# FMC_130MSPS_4CH.net
KiCad netlist of a schematic drawn in Altium Designer
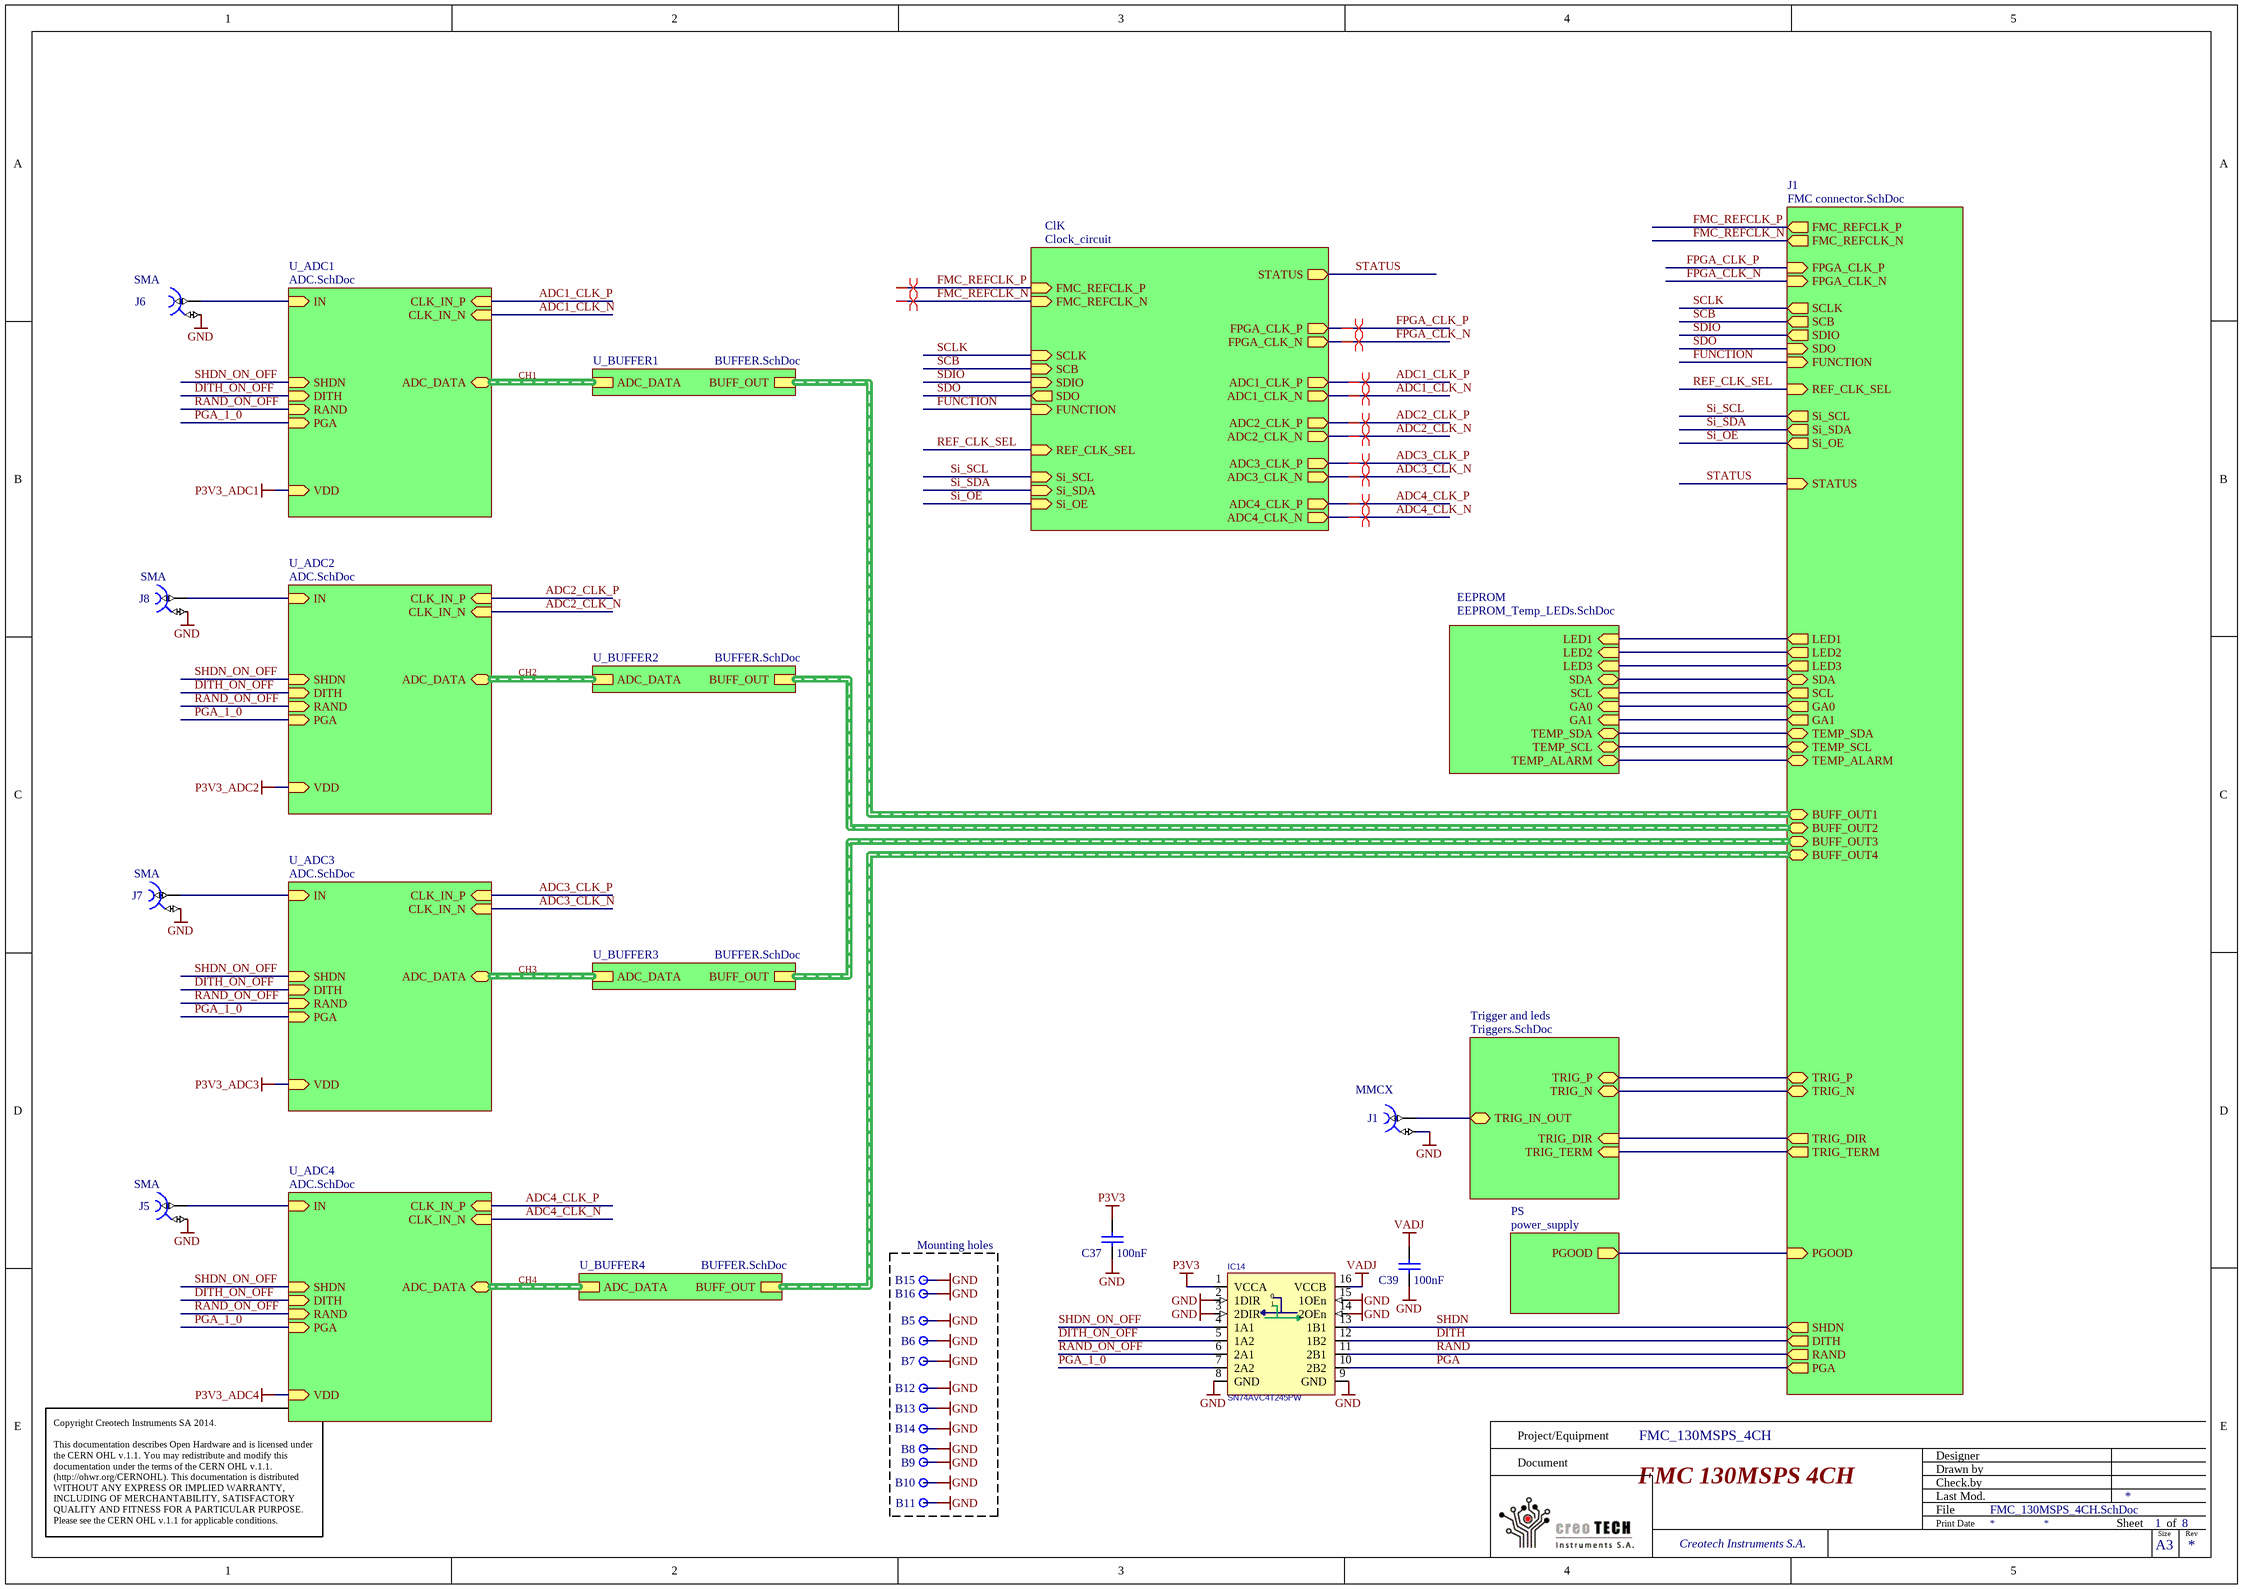
[diagram p0: FMC_130MSPS_4CH.SchDoc]

(export (version "E")
  (design (tool "Eeschema 10.0.6"))
  (components
    (comp (ref "B5")
      (value "Plated Hole")
      (footprint "MTG240_400")
      (description "Single Terminal Socket")
      (fields (field (name "PART NUMBER") "PLATED_HOLE2.4_PAD4.0") (field (name "AUTHOR") "CERN DEM JMW"))
      (libsource (lib "Eletro-mechanical") (part "Single Terminal Socket"))
    )
    (comp (ref "B6")
      (value "Plated Hole")
      (footprint "MTG240_400")
      (description "Single Terminal Socket")
      (fields (field (name "PART NUMBER") "PLATED_HOLE2.4_PAD4.0") (field (name "AUTHOR") "CERN DEM JMW"))
      (libsource (lib "Eletro-mechanical") (part "Single Terminal Socket"))
    )
    (comp (ref "B7")
      (value "Plated Hole")
      (footprint "MTG240_400")
      (description "Single Terminal Socket")
      (fields (field (name "PART NUMBER") "PLATED_HOLE2.4_PAD4.0") (field (name "AUTHOR") "CERN DEM JMW"))
      (libsource (lib "Eletro-mechanical") (part "Single Terminal Socket"))
    )
    (comp (ref "B8")
      (value "Plated Hole")
      (footprint "MTG240_400")
      (description "Single Terminal Socket")
      (fields (field (name "PART NUMBER") "PLATED_HOLE2.4_PAD4.0") (field (name "AUTHOR") "CERN DEM JMW"))
      (libsource (lib "Eletro-mechanical") (part "Single Terminal Socket"))
    )
    (comp (ref "B9")
      (value "Plated Hole")
      (footprint "MTG240_400")
      (description "Single Terminal Socket")
      (fields (field (name "PART NUMBER") "PLATED_HOLE2.4_PAD4.0") (field (name "AUTHOR") "CERN DEM JMW"))
      (libsource (lib "Eletro-mechanical") (part "Single Terminal Socket"))
    )
    (comp (ref "B10")
      (value "Plated Hole")
      (footprint "MTG240_400")
      (description "Single Terminal Socket")
      (fields (field (name "PART NUMBER") "PLATED_HOLE2.4_PAD4.0") (field (name "AUTHOR") "CERN DEM JMW"))
      (libsource (lib "Eletro-mechanical") (part "Single Terminal Socket"))
    )
    (comp (ref "B11")
      (value "Plated Hole")
      (footprint "MTG240_400")
      (description "Single Terminal Socket")
      (fields (field (name "PART NUMBER") "PLATED_HOLE2.4_PAD4.0") (field (name "AUTHOR") "CERN DEM JMW"))
      (libsource (lib "Eletro-mechanical") (part "Single Terminal Socket"))
    )
    (comp (ref "B12")
      (value "Plated Hole")
      (footprint "MTG240_400")
      (description "Single Terminal Socket")
      (fields (field (name "PART NUMBER") "PLATED_HOLE2.4_PAD4.0") (field (name "AUTHOR") "CERN DEM JMW"))
      (libsource (lib "Eletro-mechanical") (part "Single Terminal Socket"))
    )
    (comp (ref "B13")
      (value "Plated Hole")
      (footprint "MTG240_400")
      (description "Single Terminal Socket")
      (fields (field (name "PART NUMBER") "PLATED_HOLE2.4_PAD4.0") (field (name "AUTHOR") "CERN DEM JMW"))
      (libsource (lib "Eletro-mechanical") (part "Single Terminal Socket"))
    )
    (comp (ref "B14")
      (value "Plated Hole")
      (footprint "MTG240_400")
      (description "Single Terminal Socket")
      (fields (field (name "PART NUMBER") "PLATED_HOLE2.4_PAD4.0") (field (name "AUTHOR") "CERN DEM JMW"))
      (libsource (lib "Eletro-mechanical") (part "Single Terminal Socket"))
    )
    (comp (ref "B15")
      (value "Plated Hole")
      (footprint "MTG240_400")
      (description "Single Terminal Socket")
      (fields (field (name "PART NUMBER") "PLATED_HOLE2.4_PAD4.0") (field (name "AUTHOR") "CERN DEM JMW"))
      (libsource (lib "Eletro-mechanical") (part "Single Terminal Socket"))
    )
    (comp (ref "B16")
      (value "Plated Hole")
      (footprint "MTG240_400")
      (description "Single Terminal Socket")
      (fields (field (name "PART NUMBER") "PLATED_HOLE2.4_PAD4.0") (field (name "AUTHOR") "CERN DEM JMW"))
      (libsource (lib "Eletro-mechanical") (part "Single Terminal Socket"))
    )
    (comp (ref "C37")
      (value "100nF")
      (footprint "CAPC0603X33N")
      (description "Non-polarised capacitor")
      (fields
        (field (name "PART NUMBER") "CC0201_100NF_6.3V_10%_X5R")
        (field (name "VOLTAGE") "6.3V")
        (field (name "AUTHOR") "CERN DEM JLC")
      )
      (libsource (lib "Capacitors") (part "Capacitor - non polarized"))
    )
    (comp (ref "C39")
      (value "100nF")
      (footprint "CAPC0603X33N")
      (description "Non-polarised capacitor")
      (fields
        (field (name "PART NUMBER") "CC0201_100NF_6.3V_10%_X5R")
        (field (name "VOLTAGE") "6.3V")
        (field (name "AUTHOR") "CERN DEM JLC")
      )
      (libsource (lib "Capacitors") (part "Capacitor - non polarized"))
    )
    (comp (ref "IC14")
      (value "SN74AVC4T245PW")
      (description "4-BIT DUAL-SUPPLY BUS TRANSCEIVER")
      (libsource (lib "LIBRARY_SCH") (part "74AVC4T245"))
    )
    (comp (ref "J1")
      (value "Coax_1Female_1Shield")
      (footprint "HUBER-SUHNER_85_MMCX-50-0-1/111 OH")
      (fields
        (field (name "PART NUMBER") "HUBER-SUHNER_85_MMCX-50-0-1/111 OH")
        (field (name "FAMILY") "MMCX")
        (field (name "MANUFACTURER") "HUBER+SUHNER")
        (field (name "MANUFACTURER PART NUMBER") "85_MMCX-50-0-1/111 OH")
        (field (name "AUTHOR") "CERN DEM JLC")
      )
      (libsource (lib "Connectors") (part "Coax_1Female_1Shield"))
    )
    (comp (ref "J5")
      (value "Coax_1Female_1Shield")
      (footprint "JOHNSON_142-0711-301")
      (fields
        (field (name "PART NUMBER") "JOHNSON_142-0711-301")
        (field (name "FAMILY") "SMA")
        (field (name "MANUFACTURER") "JOHNSON")
        (field (name "MANUFACTURER PART NUMBER") "142-0711-301")
        (field (name "AUTHOR") "CERN DEM JLC")
      )
      (libsource (lib "Connectors") (part "Coax_1Female_1Shield"))
    )
    (comp (ref "J6")
      (value "Coax_1Female_1Shield")
      (footprint "JOHNSON_142-0711-301")
      (fields
        (field (name "PART NUMBER") "JOHNSON_142-0711-301")
        (field (name "FAMILY") "SMA")
        (field (name "MANUFACTURER") "JOHNSON")
        (field (name "MANUFACTURER PART NUMBER") "142-0711-301")
        (field (name "AUTHOR") "CERN DEM JLC")
      )
      (libsource (lib "Connectors") (part "Coax_1Female_1Shield"))
    )
    (comp (ref "J7")
      (value "Coax_1Female_1Shield")
      (footprint "JOHNSON_142-0711-301")
      (fields
        (field (name "PART NUMBER") "JOHNSON_142-0711-301")
        (field (name "FAMILY") "SMA")
        (field (name "MANUFACTURER") "JOHNSON")
        (field (name "MANUFACTURER PART NUMBER") "142-0711-301")
        (field (name "AUTHOR") "CERN DEM JLC")
      )
      (libsource (lib "Connectors") (part "Coax_1Female_1Shield"))
    )
    (comp (ref "J8")
      (value "Coax_1Female_1Shield")
      (footprint "JOHNSON_142-0711-301")
      (fields
        (field (name "PART NUMBER") "JOHNSON_142-0711-301")
        (field (name "FAMILY") "SMA")
        (field (name "MANUFACTURER") "JOHNSON")
        (field (name "MANUFACTURER PART NUMBER") "142-0711-301")
        (field (name "AUTHOR") "CERN DEM JLC")
      )
      (libsource (lib "Connectors") (part "Coax_1Female_1Shield"))
    )
  )
  (nets
    (net (code "17") (name "/DITH") (class "Default")
      (node (ref "IC14") (pin "12") (pinfunction "1B2_12") (pintype "bidirectional"))
    )
    (net (code "18") (name "/DITH_ON_OFF") (class "Default")
      (node (ref "IC14") (pin "5") (pinfunction "1A2_5") (pintype "bidirectional"))
    )
    (net (code "26") (name "/IN") (class "Default")
      (node (ref "J8") (pin "1") (pinfunction "1_1") (pintype "bidirectional"))
    )
    (net (code "27") (name "/IN_1") (class "Default")
      (node (ref "J7") (pin "1") (pinfunction "1_1") (pintype "bidirectional"))
    )
    (net (code "28") (name "/IN_2") (class "Default")
      (node (ref "J5") (pin "1") (pinfunction "1_1") (pintype "bidirectional"))
    )
    (net (code "29") (name "/IN_3") (class "Default")
      (node (ref "J6") (pin "1") (pinfunction "1_1") (pintype "bidirectional"))
    )
    (net (code "33") (name "/PGA") (class "Default")
      (node (ref "IC14") (pin "10") (pinfunction "2B2_10") (pintype "bidirectional"))
    )
    (net (code "34") (name "/PGA_1_0") (class "Default")
      (node (ref "IC14") (pin "7") (pinfunction "2A2_7") (pintype "bidirectional"))
    )
    (net (code "36") (name "/RAND") (class "Default")
      (node (ref "IC14") (pin "11") (pinfunction "2B1_11") (pintype "bidirectional"))
    )
    (net (code "37") (name "/RAND_ON_OFF") (class "Default")
      (node (ref "IC14") (pin "6") (pinfunction "2A1_6") (pintype "bidirectional"))
    )
    (net (code "45") (name "/SHDN") (class "Default")
      (node (ref "IC14") (pin "13") (pinfunction "1B1_13") (pintype "bidirectional"))
    )
    (net (code "46") (name "/SHDN_ON_OFF") (class "Default")
      (node (ref "IC14") (pin "4") (pinfunction "1A1_4") (pintype "bidirectional"))
    )
    (net (code "55") (name "/TRIG_IN_OUT") (class "Default")
      (node (ref "J1") (pin "1") (pinfunction "1_1") (pintype "bidirectional"))
    )
    (net (code "63") (name "GND") (class "Default")
      (node (ref "B10") (pin "1") (pinfunction "1_1") (pintype "passive"))
      (node (ref "B11") (pin "1") (pinfunction "1_1") (pintype "passive"))
      (node (ref "B12") (pin "1") (pinfunction "1_1") (pintype "passive"))
      (node (ref "B13") (pin "1") (pinfunction "1_1") (pintype "passive"))
      (node (ref "B14") (pin "1") (pinfunction "1_1") (pintype "passive"))
      (node (ref "B15") (pin "1") (pinfunction "1_1") (pintype "passive"))
      (node (ref "B16") (pin "1") (pinfunction "1_1") (pintype "passive"))
      (node (ref "B5") (pin "1") (pinfunction "1_1") (pintype "passive"))
      (node (ref "B6") (pin "1") (pinfunction "1_1") (pintype "passive"))
      (node (ref "B7") (pin "1") (pinfunction "1_1") (pintype "passive"))
      (node (ref "B8") (pin "1") (pinfunction "1_1") (pintype "passive"))
      (node (ref "B9") (pin "1") (pinfunction "1_1") (pintype "passive"))
      (node (ref "C37") (pin "1") (pinfunction "1_1") (pintype "passive"))
      (node (ref "C39") (pin "1") (pinfunction "1_1") (pintype "passive"))
      (node (ref "IC14") (pin "14") (pinfunction "2OEn_14") (pintype "input"))
      (node (ref "IC14") (pin "15") (pinfunction "1OEn_15") (pintype "input"))
      (node (ref "IC14") (pin "2") (pinfunction "1DIR_2") (pintype "input"))
      (node (ref "IC14") (pin "3") (pinfunction "2DIR_3") (pintype "input"))
      (node (ref "IC14") (pin "8") (pinfunction "GND_8") (pintype "power_in"))
      (node (ref "IC14") (pin "9") (pinfunction "GND_9") (pintype "power_in"))
      (node (ref "J1") (pin "2") (pinfunction "2_2") (pintype "bidirectional"))
      (node (ref "J5") (pin "2") (pinfunction "2_2") (pintype "bidirectional"))
      (node (ref "J6") (pin "2") (pinfunction "2_2") (pintype "bidirectional"))
      (node (ref "J7") (pin "2") (pinfunction "2_2") (pintype "bidirectional"))
      (node (ref "J8") (pin "2") (pinfunction "2_2") (pintype "bidirectional"))
    )
    (net (code "64") (name "P3V3") (class "Default")
      (node (ref "C37") (pin "2") (pinfunction "2_2") (pintype "passive"))
      (node (ref "IC14") (pin "1") (pinfunction "VCCA_1") (pintype "power_in"))
    )
    (net (code "69") (name "VADJ") (class "Default")
      (node (ref "C39") (pin "2") (pinfunction "2_2") (pintype "passive"))
      (node (ref "IC14") (pin "16") (pinfunction "VCCB_16") (pintype "power_in"))
    )
  )
)
